# RasPi-Hi_Power.net
KiCad netlist of a schematic drawn in EAGLE
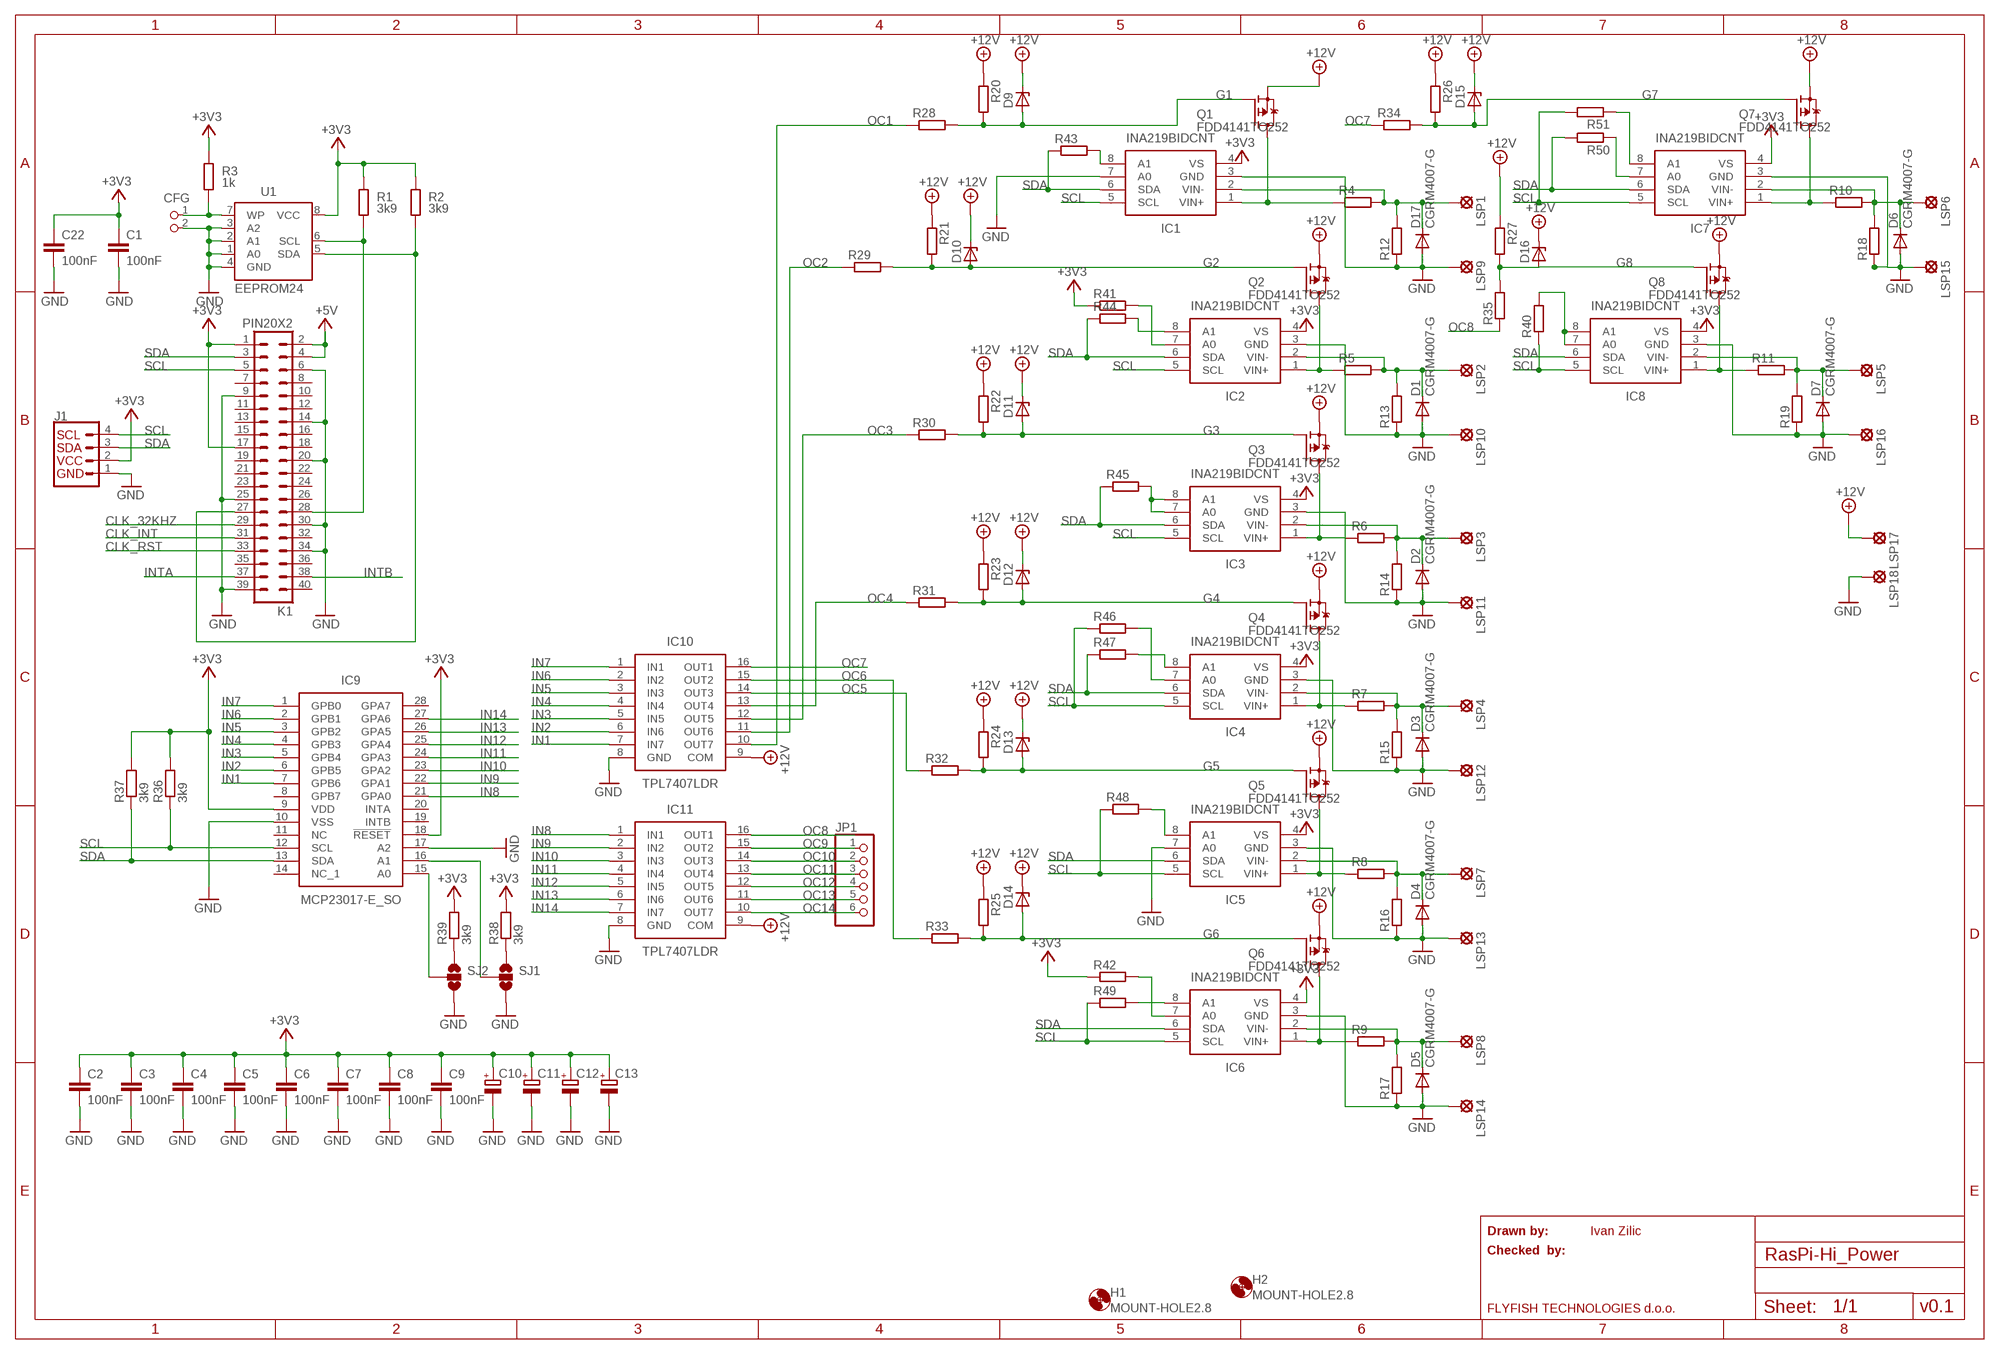
[diagram p0: schematic, sheet 1]

(export (version "E")
  (design (tool "Eeschema 10.0.6"))
  (components
    (comp (ref "C1")
      (value "100nF")
      (footprint "eagle-import:C0805K")
      (libsource (lib "eagle-import") (part "C-EUC0805K"))
    )
    (comp (ref "C2")
      (value "100nF")
      (footprint "eagle-import:C0805K")
      (libsource (lib "eagle-import") (part "C-EUC0805K"))
    )
    (comp (ref "C3")
      (value "100nF")
      (footprint "eagle-import:C0805K")
      (libsource (lib "eagle-import") (part "C-EUC0805K"))
    )
    (comp (ref "C4")
      (value "100nF")
      (footprint "eagle-import:C0805K")
      (libsource (lib "eagle-import") (part "C-EUC0805K"))
    )
    (comp (ref "C5")
      (value "100nF")
      (footprint "eagle-import:C0805K")
      (libsource (lib "eagle-import") (part "C-EUC0805K"))
    )
    (comp (ref "C6")
      (value "100nF")
      (footprint "eagle-import:C0805K")
      (libsource (lib "eagle-import") (part "C-EUC0805K"))
    )
    (comp (ref "C7")
      (value "100nF")
      (footprint "eagle-import:C0805K")
      (libsource (lib "eagle-import") (part "C-EUC0805K"))
    )
    (comp (ref "C8")
      (value "100nF")
      (footprint "eagle-import:C0805K")
      (libsource (lib "eagle-import") (part "C-EUC0805K"))
    )
    (comp (ref "C9")
      (value "100nF")
      (footprint "eagle-import:C0805K")
      (libsource (lib "eagle-import") (part "C-EUC0805K"))
    )
    (comp (ref "C10")
      (value "CPOL-EUSMCD")
      (footprint "eagle-import:SMC_D")
      (libsource (lib "eagle-import") (part "CPOL-EUSMCD"))
    )
    (comp (ref "C11")
      (value "CPOL-EUSMCD")
      (footprint "eagle-import:SMC_D")
      (libsource (lib "eagle-import") (part "CPOL-EUSMCD"))
    )
    (comp (ref "C12")
      (value "CPOL-EUSMCD")
      (footprint "eagle-import:SMC_D")
      (libsource (lib "eagle-import") (part "CPOL-EUSMCD"))
    )
    (comp (ref "C13")
      (value "CPOL-EUSMCD")
      (footprint "eagle-import:SMC_D")
      (libsource (lib "eagle-import") (part "CPOL-EUSMCD"))
    )
    (comp (ref "C22")
      (value "100nF")
      (footprint "eagle-import:C0805K")
      (libsource (lib "eagle-import") (part "C-EUC0805K"))
    )
    (comp (ref "CFG")
      (value "PIN2_100")
      (footprint "eagle-import:PIN_W_2")
      (libsource (lib "eagle-import") (part "PIN2_100"))
    )
    (comp (ref "D1")
      (value "CGRM4007-G")
      (footprint "eagle-import:SOD-123_MINI-SMA")
      (libsource (lib "eagle-import") (part "CGRM400-G7"))
    )
    (comp (ref "D2")
      (value "CGRM4007-G")
      (footprint "eagle-import:SOD-123_MINI-SMA")
      (libsource (lib "eagle-import") (part "CGRM400-G7"))
    )
    (comp (ref "D3")
      (value "CGRM4007-G")
      (footprint "eagle-import:SOD-123_MINI-SMA")
      (libsource (lib "eagle-import") (part "CGRM400-G7"))
    )
    (comp (ref "D4")
      (value "CGRM4007-G")
      (footprint "eagle-import:SOD-123_MINI-SMA")
      (libsource (lib "eagle-import") (part "CGRM400-G7"))
    )
    (comp (ref "D5")
      (value "CGRM4007-G")
      (footprint "eagle-import:SOD-123_MINI-SMA")
      (libsource (lib "eagle-import") (part "CGRM400-G7"))
    )
    (comp (ref "D6")
      (value "CGRM4007-G")
      (footprint "eagle-import:SOD-123_MINI-SMA")
      (libsource (lib "eagle-import") (part "CGRM400-G7"))
    )
    (comp (ref "D7")
      (value "CGRM4007-G")
      (footprint "eagle-import:SOD-123_MINI-SMA")
      (libsource (lib "eagle-import") (part "CGRM400-G7"))
    )
    (comp (ref "D9")
      (value "ZENER-DIODESOT23")
      (footprint "eagle-import:SOT23")
      (libsource (lib "eagle-import") (part "ZENER-DIODESOT23"))
    )
    (comp (ref "D10")
      (value "ZENER-DIODESOT23")
      (footprint "eagle-import:SOT23")
      (libsource (lib "eagle-import") (part "ZENER-DIODESOT23"))
    )
    (comp (ref "D11")
      (value "ZENER-DIODESOT23")
      (footprint "eagle-import:SOT23")
      (libsource (lib "eagle-import") (part "ZENER-DIODESOT23"))
    )
    (comp (ref "D12")
      (value "ZENER-DIODESOT23")
      (footprint "eagle-import:SOT23")
      (libsource (lib "eagle-import") (part "ZENER-DIODESOT23"))
    )
    (comp (ref "D13")
      (value "ZENER-DIODESOT23")
      (footprint "eagle-import:SOT23")
      (libsource (lib "eagle-import") (part "ZENER-DIODESOT23"))
    )
    (comp (ref "D14")
      (value "ZENER-DIODESOT23")
      (footprint "eagle-import:SOT23")
      (libsource (lib "eagle-import") (part "ZENER-DIODESOT23"))
    )
    (comp (ref "D15")
      (value "ZENER-DIODESOT23")
      (footprint "eagle-import:SOT23")
      (libsource (lib "eagle-import") (part "ZENER-DIODESOT23"))
    )
    (comp (ref "D16")
      (value "ZENER-DIODESOT23")
      (footprint "eagle-import:SOT23")
      (libsource (lib "eagle-import") (part "ZENER-DIODESOT23"))
    )
    (comp (ref "D17")
      (value "CGRM4007-G")
      (footprint "eagle-import:SOD-123_MINI-SMA")
      (libsource (lib "eagle-import") (part "CGRM400-G7"))
    )
    (comp (ref "H1")
      (value "MOUNT-HOLE2.8")
      (footprint "eagle-import:2,8")
      (libsource (lib "eagle-import") (part "MOUNT-HOLE2.8"))
    )
    (comp (ref "H2")
      (value "MOUNT-HOLE2.8")
      (footprint "eagle-import:2,8")
      (libsource (lib "eagle-import") (part "MOUNT-HOLE2.8"))
    )
    (comp (ref "IC1")
      (value "INA219BIDCNT")
      (footprint "eagle-import:SOT65P280X145-8N")
      (fields (field (name "RS_PART_NUMBER") "7300556P"))
      (libsource (lib "eagle-import") (part "INA219BIDCNT"))
    )
    (comp (ref "IC2")
      (value "INA219BIDCNT")
      (footprint "eagle-import:SOT65P280X145-8N")
      (fields (field (name "RS_PART_NUMBER") "7300556P"))
      (libsource (lib "eagle-import") (part "INA219BIDCNT"))
    )
    (comp (ref "IC3")
      (value "INA219BIDCNT")
      (footprint "eagle-import:SOT65P280X145-8N")
      (fields (field (name "RS_PART_NUMBER") "7300556P"))
      (libsource (lib "eagle-import") (part "INA219BIDCNT"))
    )
    (comp (ref "IC4")
      (value "INA219BIDCNT")
      (footprint "eagle-import:SOT65P280X145-8N")
      (fields (field (name "RS_PART_NUMBER") "7300556P"))
      (libsource (lib "eagle-import") (part "INA219BIDCNT"))
    )
    (comp (ref "IC5")
      (value "INA219BIDCNT")
      (footprint "eagle-import:SOT65P280X145-8N")
      (fields (field (name "RS_PART_NUMBER") "7300556P"))
      (libsource (lib "eagle-import") (part "INA219BIDCNT"))
    )
    (comp (ref "IC6")
      (value "INA219BIDCNT")
      (footprint "eagle-import:SOT65P280X145-8N")
      (fields (field (name "RS_PART_NUMBER") "7300556P"))
      (libsource (lib "eagle-import") (part "INA219BIDCNT"))
    )
    (comp (ref "IC7")
      (value "INA219BIDCNT")
      (footprint "eagle-import:SOT65P280X145-8N")
      (fields (field (name "RS_PART_NUMBER") "7300556P"))
      (libsource (lib "eagle-import") (part "INA219BIDCNT"))
    )
    (comp (ref "IC8")
      (value "INA219BIDCNT")
      (footprint "eagle-import:SOT65P280X145-8N")
      (fields (field (name "RS_PART_NUMBER") "7300556P"))
      (libsource (lib "eagle-import") (part "INA219BIDCNT"))
    )
    (comp (ref "IC9")
      (value "MCP23017-E_SO")
      (footprint "eagle-import:SOIC127P1030X265-28N")
      (fields
        (field (name "MANUFACTURER_PART_NUMBER") "MCP23017-E/SO")
        (field (name "RS_PART_NUMBER") "0403816P")
      )
      (libsource (lib "eagle-import") (part "MCP23017-E_SO"))
    )
    (comp (ref "IC10")
      (value "TPL7407LDR")
      (footprint "eagle-import:SOIC127P600X175-16N")
      (libsource (lib "eagle-import") (part "TPL7407LDR"))
    )
    (comp (ref "IC11")
      (value "TPL7407LDR")
      (footprint "eagle-import:SOIC127P600X175-16N")
      (libsource (lib "eagle-import") (part "TPL7407LDR"))
    )
    (comp (ref "J1")
      (value "I2C_STANDARD")
      (footprint "eagle-import:1X04")
      (libsource (lib "eagle-import") (part "I2C_STANDARD"))
    )
    (comp (ref "JP1")
      (value "PINHD-1X6")
      (footprint "eagle-import:1X06")
      (libsource (lib "eagle-import") (part "PINHD-1X6"))
    )
    (comp (ref "K1")
      (value "PIN20X2")
      (footprint "eagle-import:PIN_20X2")
      (libsource (lib "eagle-import") (part "PIN20X2"))
    )
    (comp (ref "LSP1")
      (value "SE13")
      (footprint "eagle-import:SE13")
      (libsource (lib "eagle-import") (part "SE13"))
    )
    (comp (ref "LSP2")
      (value "SE13")
      (footprint "eagle-import:SE13")
      (libsource (lib "eagle-import") (part "SE13"))
    )
    (comp (ref "LSP3")
      (value "SE13")
      (footprint "eagle-import:SE13")
      (libsource (lib "eagle-import") (part "SE13"))
    )
    (comp (ref "LSP4")
      (value "SE13")
      (footprint "eagle-import:SE13")
      (libsource (lib "eagle-import") (part "SE13"))
    )
    (comp (ref "LSP5")
      (value "SE13")
      (footprint "eagle-import:SE13")
      (libsource (lib "eagle-import") (part "SE13"))
    )
    (comp (ref "LSP6")
      (value "SE13")
      (footprint "eagle-import:SE13")
      (libsource (lib "eagle-import") (part "SE13"))
    )
    (comp (ref "LSP7")
      (value "SE13")
      (footprint "eagle-import:SE13")
      (libsource (lib "eagle-import") (part "SE13"))
    )
    (comp (ref "LSP8")
      (value "SE13")
      (footprint "eagle-import:SE13")
      (libsource (lib "eagle-import") (part "SE13"))
    )
    (comp (ref "LSP9")
      (value "SE13")
      (footprint "eagle-import:SE13")
      (libsource (lib "eagle-import") (part "SE13"))
    )
    (comp (ref "LSP10")
      (value "SE13")
      (footprint "eagle-import:SE13")
      (libsource (lib "eagle-import") (part "SE13"))
    )
    (comp (ref "LSP11")
      (value "SE13")
      (footprint "eagle-import:SE13")
      (libsource (lib "eagle-import") (part "SE13"))
    )
    (comp (ref "LSP12")
      (value "SE13")
      (footprint "eagle-import:SE13")
      (libsource (lib "eagle-import") (part "SE13"))
    )
    (comp (ref "LSP13")
      (value "SE13")
      (footprint "eagle-import:SE13")
      (libsource (lib "eagle-import") (part "SE13"))
    )
    (comp (ref "LSP14")
      (value "SE13")
      (footprint "eagle-import:SE13")
      (libsource (lib "eagle-import") (part "SE13"))
    )
    (comp (ref "LSP15")
      (value "SE13")
      (footprint "eagle-import:SE13")
      (libsource (lib "eagle-import") (part "SE13"))
    )
    (comp (ref "LSP16")
      (value "SE13")
      (footprint "eagle-import:SE13")
      (libsource (lib "eagle-import") (part "SE13"))
    )
    (comp (ref "LSP17")
      (value "SE13")
      (footprint "eagle-import:SE13")
      (libsource (lib "eagle-import") (part "SE13"))
    )
    (comp (ref "LSP18")
      (value "SE13")
      (footprint "eagle-import:SE13")
      (libsource (lib "eagle-import") (part "SE13"))
    )
    (comp (ref "Q1")
      (value "FDD4141TO252")
      (footprint "eagle-import:TO252")
      (libsource (lib "eagle-import") (part "FDD4141TO252"))
    )
    (comp (ref "Q2")
      (value "FDD4141TO252")
      (footprint "eagle-import:TO252")
      (libsource (lib "eagle-import") (part "FDD4141TO252"))
    )
    (comp (ref "Q3")
      (value "FDD4141TO252")
      (footprint "eagle-import:TO252")
      (libsource (lib "eagle-import") (part "FDD4141TO252"))
    )
    (comp (ref "Q4")
      (value "FDD4141TO252")
      (footprint "eagle-import:TO252")
      (libsource (lib "eagle-import") (part "FDD4141TO252"))
    )
    (comp (ref "Q5")
      (value "FDD4141TO252")
      (footprint "eagle-import:TO252")
      (libsource (lib "eagle-import") (part "FDD4141TO252"))
    )
    (comp (ref "Q6")
      (value "FDD4141TO252")
      (footprint "eagle-import:TO252")
      (libsource (lib "eagle-import") (part "FDD4141TO252"))
    )
    (comp (ref "Q7")
      (value "FDD4141TO252")
      (footprint "eagle-import:TO252")
      (libsource (lib "eagle-import") (part "FDD4141TO252"))
    )
    (comp (ref "Q8")
      (value "FDD4141TO252")
      (footprint "eagle-import:TO252")
      (libsource (lib "eagle-import") (part "FDD4141TO252"))
    )
    (comp (ref "R1")
      (value "3k9")
      (footprint "eagle-import:M0805")
      (fields (field (name "TOLERANCE") "5%"))
      (libsource (lib "eagle-import") (part "resistor_348_R-EU_M0805"))
    )
    (comp (ref "R2")
      (value "3k9")
      (footprint "eagle-import:M0805")
      (fields (field (name "TOLERANCE") "5%"))
      (libsource (lib "eagle-import") (part "resistor_348_R-EU_M0805"))
    )
    (comp (ref "R3")
      (value "1k")
      (footprint "eagle-import:M0805")
      (fields (field (name "TOLERANCE") "5%"))
      (libsource (lib "eagle-import") (part "resistor_348_R-EU_M0805"))
    )
    (comp (ref "R4")
      (value "R-EU_R1210")
      (footprint "eagle-import:R1210")
      (libsource (lib "eagle-import") (part "R-EU_R1210"))
    )
    (comp (ref "R5")
      (value "R-EU_R1210")
      (footprint "eagle-import:R1210")
      (libsource (lib "eagle-import") (part "R-EU_R1210"))
    )
    (comp (ref "R6")
      (value "R-EU_R1210")
      (footprint "eagle-import:R1210")
      (libsource (lib "eagle-import") (part "R-EU_R1210"))
    )
    (comp (ref "R7")
      (value "R-EU_R1210")
      (footprint "eagle-import:R1210")
      (libsource (lib "eagle-import") (part "R-EU_R1210"))
    )
    (comp (ref "R8")
      (value "R-EU_R1210")
      (footprint "eagle-import:R1210")
      (libsource (lib "eagle-import") (part "R-EU_R1210"))
    )
    (comp (ref "R9")
      (value "R-EU_R1210")
      (footprint "eagle-import:R1210")
      (libsource (lib "eagle-import") (part "R-EU_R1210"))
    )
    (comp (ref "R10")
      (value "R-EU_R1210")
      (footprint "eagle-import:R1210")
      (libsource (lib "eagle-import") (part "R-EU_R1210"))
    )
    (comp (ref "R11")
      (value "R-EU_R1210")
      (footprint "eagle-import:R1210")
      (libsource (lib "eagle-import") (part "R-EU_R1210"))
    )
    (comp (ref "R12")
      (value "R-EU_R0805")
      (footprint "eagle-import:R0805")
      (libsource (lib "eagle-import") (part "R-EU_R0805"))
    )
    (comp (ref "R13")
      (value "R-EU_R0805")
      (footprint "eagle-import:R0805")
      (libsource (lib "eagle-import") (part "R-EU_R0805"))
    )
    (comp (ref "R14")
      (value "R-EU_R0805")
      (footprint "eagle-import:R0805")
      (libsource (lib "eagle-import") (part "R-EU_R0805"))
    )
    (comp (ref "R15")
      (value "R-EU_R0805")
      (footprint "eagle-import:R0805")
      (libsource (lib "eagle-import") (part "R-EU_R0805"))
    )
    (comp (ref "R16")
      (value "R-EU_R0805")
      (footprint "eagle-import:R0805")
      (libsource (lib "eagle-import") (part "R-EU_R0805"))
    )
    (comp (ref "R17")
      (value "R-EU_R0805")
      (footprint "eagle-import:R0805")
      (libsource (lib "eagle-import") (part "R-EU_R0805"))
    )
    (comp (ref "R18")
      (value "R-EU_R0805")
      (footprint "eagle-import:R0805")
      (libsource (lib "eagle-import") (part "R-EU_R0805"))
    )
    (comp (ref "R19")
      (value "R-EU_R0805")
      (footprint "eagle-import:R0805")
      (libsource (lib "eagle-import") (part "R-EU_R0805"))
    )
    (comp (ref "R20")
      (value "R-EU_R0805")
      (footprint "eagle-import:R0805")
      (libsource (lib "eagle-import") (part "R-EU_R0805"))
    )
    (comp (ref "R21")
      (value "R-EU_R0805")
      (footprint "eagle-import:R0805")
      (libsource (lib "eagle-import") (part "R-EU_R0805"))
    )
    (comp (ref "R22")
      (value "R-EU_R0805")
      (footprint "eagle-import:R0805")
      (libsource (lib "eagle-import") (part "R-EU_R0805"))
    )
    (comp (ref "R23")
      (value "R-EU_R0805")
      (footprint "eagle-import:R0805")
      (libsource (lib "eagle-import") (part "R-EU_R0805"))
    )
    (comp (ref "R24")
      (value "R-EU_R0805")
      (footprint "eagle-import:R0805")
      (libsource (lib "eagle-import") (part "R-EU_R0805"))
    )
    (comp (ref "R25")
      (value "R-EU_R0805")
      (footprint "eagle-import:R0805")
      (libsource (lib "eagle-import") (part "R-EU_R0805"))
    )
    (comp (ref "R26")
      (value "R-EU_R0805")
      (footprint "eagle-import:R0805")
      (libsource (lib "eagle-import") (part "R-EU_R0805"))
    )
    (comp (ref "R27")
      (value "R-EU_R0805")
      (footprint "eagle-import:R0805")
      (libsource (lib "eagle-import") (part "R-EU_R0805"))
    )
    (comp (ref "R28")
      (value "R-EU_R0805")
      (footprint "eagle-import:R0805")
      (libsource (lib "eagle-import") (part "R-EU_R0805"))
    )
    (comp (ref "R29")
      (value "R-EU_R0805")
      (footprint "eagle-import:R0805")
      (libsource (lib "eagle-import") (part "R-EU_R0805"))
    )
    (comp (ref "R30")
      (value "R-EU_R0805")
      (footprint "eagle-import:R0805")
      (libsource (lib "eagle-import") (part "R-EU_R0805"))
    )
    (comp (ref "R31")
      (value "R-EU_R0805")
      (footprint "eagle-import:R0805")
      (libsource (lib "eagle-import") (part "R-EU_R0805"))
    )
    (comp (ref "R32")
      (value "R-EU_R0805")
      (footprint "eagle-import:R0805")
      (libsource (lib "eagle-import") (part "R-EU_R0805"))
    )
    (comp (ref "R33")
      (value "R-EU_R0805")
      (footprint "eagle-import:R0805")
      (libsource (lib "eagle-import") (part "R-EU_R0805"))
    )
    (comp (ref "R34")
      (value "R-EU_R0805")
      (footprint "eagle-import:R0805")
      (libsource (lib "eagle-import") (part "R-EU_R0805"))
    )
    (comp (ref "R35")
      (value "R-EU_R0805")
      (footprint "eagle-import:R0805")
      (libsource (lib "eagle-import") (part "R-EU_R0805"))
    )
    (comp (ref "R36")
      (value "3k9")
      (footprint "eagle-import:M0805")
      (fields (field (name "TOLERANCE") "5%"))
      (libsource (lib "eagle-import") (part "resistor_348_R-EU_M0805"))
    )
    (comp (ref "R37")
      (value "3k9")
      (footprint "eagle-import:M0805")
      (fields (field (name "TOLERANCE") "5%"))
      (libsource (lib "eagle-import") (part "resistor_348_R-EU_M0805"))
    )
    (comp (ref "R38")
      (value "3k9")
      (footprint "eagle-import:R0603")
      (fields (field (name "TOLERANCE") "5%"))
      (libsource (lib "eagle-import") (part "resistor_348_R-EU_R0603"))
    )
    (comp (ref "R39")
      (value "3k9")
      (footprint "eagle-import:R0603")
      (fields (field (name "TOLERANCE") "5%"))
      (libsource (lib "eagle-import") (part "resistor_348_R-EU_R0603"))
    )
    (comp (ref "R40")
      (value "R-EU_R0603")
      (footprint "eagle-import:R0603")
      (libsource (lib "eagle-import") (part "R-EU_R0603"))
    )
    (comp (ref "R41")
      (value "R-EU_R0805")
      (footprint "eagle-import:R0805")
      (libsource (lib "eagle-import") (part "R-EU_R0805"))
    )
    (comp (ref "R42")
      (value "R-EU_R0805")
      (footprint "eagle-import:R0805")
      (libsource (lib "eagle-import") (part "R-EU_R0805"))
    )
    (comp (ref "R43")
      (value "R-EU_R0805")
      (footprint "eagle-import:R0805")
      (libsource (lib "eagle-import") (part "R-EU_R0805"))
    )
    (comp (ref "R44")
      (value "R-EU_R0805")
      (footprint "eagle-import:R0805")
      (libsource (lib "eagle-import") (part "R-EU_R0805"))
    )
    (comp (ref "R45")
      (value "R-EU_R0805")
      (footprint "eagle-import:R0805")
      (libsource (lib "eagle-import") (part "R-EU_R0805"))
    )
    (comp (ref "R46")
      (value "R-EU_R0805")
      (footprint "eagle-import:R0805")
      (libsource (lib "eagle-import") (part "R-EU_R0805"))
    )
    (comp (ref "R47")
      (value "R-EU_R0805")
      (footprint "eagle-import:R0805")
      (libsource (lib "eagle-import") (part "R-EU_R0805"))
    )
    (comp (ref "R48")
      (value "R-EU_R0805")
      (footprint "eagle-import:R0805")
      (libsource (lib "eagle-import") (part "R-EU_R0805"))
    )
    (comp (ref "R49")
      (value "R-EU_R0805")
      (footprint "eagle-import:R0805")
      (libsource (lib "eagle-import") (part "R-EU_R0805"))
    )
    (comp (ref "R50")
      (value "R-EU_R0805")
      (footprint "eagle-import:R0805")
      (libsource (lib "eagle-import") (part "R-EU_R0805"))
    )
    (comp (ref "R51")
      (value "R-EU_R0805")
      (footprint "eagle-import:R0805")
      (libsource (lib "eagle-import") (part "R-EU_R0805"))
    )
    (comp (ref "SJ1")
      (value "SOLDERJUMPER_2WAYT")
      (footprint "eagle-import:SJ_2")
      (libsource (lib "eagle-import") (part "SOLDERJUMPER_2WAYT"))
    )
    (comp (ref "SJ2")
      (value "SOLDERJUMPER_2WAYT")
      (footprint "eagle-import:SJ_2")
      (libsource (lib "eagle-import") (part "SOLDERJUMPER_2WAYT"))
    )
    (comp (ref "U1")
      (value "EEPROM24")
      (footprint "eagle-import:SOIC8")
      (libsource (lib "eagle-import") (part "EEPROM24"))
    )
  )
  (nets
    (net (code "1") (name "+3V3") (class "Default")
      (node (ref "C1") (pin "1") (pinfunction "1_1") (pintype "passive"))
      (node (ref "C10") (pin "+") (pinfunction "+_+") (pintype "passive"))
      (node (ref "C11") (pin "+") (pinfunction "+_+") (pintype "passive"))
      (node (ref "C12") (pin "+") (pinfunction "+_+") (pintype "passive"))
      (node (ref "C13") (pin "+") (pinfunction "+_+") (pintype "passive"))
      (node (ref "C2") (pin "1") (pinfunction "1_1") (pintype "passive"))
      (node (ref "C22") (pin "1") (pinfunction "1_1") (pintype "passive"))
      (node (ref "C3") (pin "1") (pinfunction "1_1") (pintype "passive"))
      (node (ref "C4") (pin "1") (pinfunction "1_1") (pintype "passive"))
      (node (ref "C5") (pin "1") (pinfunction "1_1") (pintype "passive"))
      (node (ref "C6") (pin "1") (pinfunction "1_1") (pintype "passive"))
      (node (ref "C7") (pin "1") (pinfunction "1_1") (pintype "passive"))
      (node (ref "C8") (pin "1") (pinfunction "1_1") (pintype "passive"))
      (node (ref "C9") (pin "1") (pinfunction "1_1") (pintype "passive"))
      (node (ref "IC1") (pin "4") (pinfunction "VS_4") (pintype "passive"))
      (node (ref "IC2") (pin "4") (pinfunction "VS_4") (pintype "passive"))
      (node (ref "IC3") (pin "4") (pinfunction "VS_4") (pintype "passive"))
      (node (ref "IC4") (pin "4") (pinfunction "VS_4") (pintype "passive"))
      (node (ref "IC5") (pin "4") (pinfunction "VS_4") (pintype "passive"))
      (node (ref "IC6") (pin "4") (pinfunction "VS_4") (pintype "passive"))
      (node (ref "IC7") (pin "4") (pinfunction "VS_4") (pintype "passive"))
      (node (ref "IC8") (pin "4") (pinfunction "VS_4") (pintype "passive"))
      (node (ref "IC9") (pin "18") (pinfunction "~{RESET}_18") (pintype "passive"))
      (node (ref "IC9") (pin "9") (pinfunction "VDD_9") (pintype "power_in"))
      (node (ref "J1") (pin "2") (pinfunction "2_2") (pintype "power_in"))
      (node (ref "K1") (pin "1") (pinfunction "1_1") (pintype "passive"))
      (node (ref "K1") (pin "17") (pinfunction "17_17") (pintype "passive"))
      (node (ref "R1") (pin "2") (pinfunction "2_2") (pintype "passive"))
      (node (ref "R2") (pin "2") (pinfunction "2_2") (pintype "passive"))
      (node (ref "R3") (pin "2") (pinfunction "2_2") (pintype "passive"))
      (node (ref "R36") (pin "2") (pinfunction "2_2") (pintype "passive"))
      (node (ref "R37") (pin "2") (pinfunction "2_2") (pintype "passive"))
      (node (ref "R38") (pin "2") (pinfunction "2_2") (pintype "passive"))
      (node (ref "R39") (pin "2") (pinfunction "2_2") (pintype "passive"))
      (node (ref "R41") (pin "1") (pinfunction "1_1") (pintype "passive"))
      (node (ref "R42") (pin "1") (pinfunction "1_1") (pintype "passive"))
      (node (ref "U1") (pin "8") (pinfunction "VCC_8") (pintype "power_in"))
    )
    (net (code "2") (name "+5V") (class "Default")
      (node (ref "K1") (pin "2") (pinfunction "2_2") (pintype "passive"))
      (node (ref "K1") (pin "4") (pinfunction "4_4") (pintype "passive"))
    )
    (net (code "3") (name "+12V") (class "Default")
      (node (ref "D10") (pin "3") (pinfunction "C_3") (pintype "passive"))
      (node (ref "D11") (pin "3") (pinfunction "C_3") (pintype "passive"))
      (node (ref "D12") (pin "3") (pinfunction "C_3") (pintype "passive"))
      (node (ref "D13") (pin "3") (pinfunction "C_3") (pintype "passive"))
      (node (ref "D14") (pin "3") (pinfunction "C_3") (pintype "passive"))
      (node (ref "D15") (pin "3") (pinfunction "C_3") (pintype "passive"))
      (node (ref "D16") (pin "3") (pinfunction "C_3") (pintype "passive"))
      (node (ref "D9") (pin "3") (pinfunction "C_3") (pintype "passive"))
      (node (ref "IC10") (pin "9") (pinfunction "COM_9") (pintype "power_in"))
      (node (ref "IC11") (pin "9") (pinfunction "COM_9") (pintype "power_in"))
      (node (ref "LSP17") (pin "MP") (pinfunction "MP_MP") (pintype "passive"))
      (node (ref "Q1") (pin "2") (pinfunction "S_2") (pintype "passive"))
      (node (ref "Q2") (pin "2") (pinfunction "S_2") (pintype "passive"))
      (node (ref "Q3") (pin "2") (pinfunction "S_2") (pintype "passive"))
      (node (ref "Q4") (pin "2") (pinfunction "S_2") (pintype "passive"))
      (node (ref "Q5") (pin "2") (pinfunction "S_2") (pintype "passive"))
      (node (ref "Q6") (pin "2") (pinfunction "S_2") (pintype "passive"))
      (node (ref "Q7") (pin "2") (pinfunction "S_2") (pintype "passive"))
      (node (ref "Q8") (pin "2") (pinfunction "S_2") (pintype "passive"))
      (node (ref "R20") (pin "1") (pinfunction "1_1") (pintype "passive"))
      (node (ref "R21") (pin "1") (pinfunction "1_1") (pintype "passive"))
      (node (ref "R22") (pin "1") (pinfunction "1_1") (pintype "passive"))
      (node (ref "R23") (pin "1") (pinfunction "1_1") (pintype "passive"))
      (node (ref "R24") (pin "1") (pinfunction "1_1") (pintype "passive"))
      (node (ref "R25") (pin "1") (pinfunction "1_1") (pintype "passive"))
      (node (ref "R26") (pin "1") (pinfunction "1_1") (pintype "passive"))
      (node (ref "R27") (pin "1") (pinfunction "1_1") (pintype "passive"))
    )
    (net (code "4") (name "/CLK_32KHZ") (class "Default")
      (node (ref "K1") (pin "29") (pinfunction "29_29") (pintype "passive"))
    )
    (net (code "5") (name "/CLK_INT") (class "Default")
      (node (ref "K1") (pin "31") (pinfunction "31_31") (pintype "passive"))
    )
    (net (code "6") (name "/CLK_RST") (class "Default")
      (node (ref "K1") (pin "33") (pinfunction "33_33") (pintype "passive"))
    )
    (net (code "7") (name "/G1") (class "Default")
      (node (ref "D9") (pin "1") (pinfunction "A_1") (pintype "passive"))
      (node (ref "Q1") (pin "1") (pinfunction "G_1") (pintype "passive"))
      (node (ref "R20") (pin "2") (pinfunction "2_2") (pintype "passive"))
      (node (ref "R28") (pin "2") (pinfunction "2_2") (pintype "passive"))
    )
    (net (code "8") (name "/G2") (class "Default")
      (node (ref "D10") (pin "1") (pinfunction "A_1") (pintype "passive"))
      (node (ref "Q2") (pin "1") (pinfunction "G_1") (pintype "passive"))
      (node (ref "R21") (pin "2") (pinfunction "2_2") (pintype "passive"))
      (node (ref "R29") (pin "2") (pinfunction "2_2") (pintype "passive"))
    )
    (net (code "9") (name "/G3") (class "Default")
      (node (ref "D11") (pin "1") (pinfunction "A_1") (pintype "passive"))
      (node (ref "Q3") (pin "1") (pinfunction "G_1") (pintype "passive"))
      (node (ref "R22") (pin "2") (pinfunction "2_2") (pintype "passive"))
      (node (ref "R30") (pin "2") (pinfunction "2_2") (pintype "passive"))
    )
    (net (code "10") (name "/G4") (class "Default")
      (node (ref "D12") (pin "1") (pinfunction "A_1") (pintype "passive"))
      (node (ref "Q4") (pin "1") (pinfunction "G_1") (pintype "passive"))
      (node (ref "R23") (pin "2") (pinfunction "2_2") (pintype "passive"))
      (node (ref "R31") (pin "2") (pinfunction "2_2") (pintype "passive"))
    )
    (net (code "11") (name "/G5") (class "Default")
      (node (ref "D13") (pin "1") (pinfunction "A_1") (pintype "passive"))
      (node (ref "Q5") (pin "1") (pinfunction "G_1") (pintype "passive"))
      (node (ref "R24") (pin "2") (pinfunction "2_2") (pintype "passive"))
      (node (ref "R32") (pin "2") (pinfunction "2_2") (pintype "passive"))
    )
    (net (code "12") (name "/G6") (class "Default")
      (node (ref "D14") (pin "1") (pinfunction "A_1") (pintype "passive"))
      (node (ref "Q6") (pin "1") (pinfunction "G_1") (pintype "passive"))
      (node (ref "R25") (pin "2") (pinfunction "2_2") (pintype "passive"))
      (node (ref "R33") (pin "2") (pinfunction "2_2") (pintype "passive"))
    )
    (net (code "13") (name "/G7") (class "Default")
      (node (ref "D15") (pin "1") (pinfunction "A_1") (pintype "passive"))
      (node (ref "Q7") (pin "1") (pinfunction "G_1") (pintype "passive"))
      (node (ref "R26") (pin "2") (pinfunction "2_2") (pintype "passive"))
      (node (ref "R34") (pin "2") (pinfunction "2_2") (pintype "passive"))
    )
    (net (code "14") (name "/G8") (class "Default")
      (node (ref "D16") (pin "1") (pinfunction "A_1") (pintype "passive"))
      (node (ref "Q8") (pin "1") (pinfunction "G_1") (pintype "passive"))
      (node (ref "R27") (pin "2") (pinfunction "2_2") (pintype "passive"))
      (node (ref "R35") (pin "2") (pinfunction "2_2") (pintype "passive"))
    )
    (net (code "15") (name "/IN1") (class "Default")
      (node (ref "IC10") (pin "7") (pinfunction "IN7_7") (pintype "input"))
      (node (ref "IC9") (pin "7") (pinfunction "GPB6_7") (pintype "passive"))
    )
    (net (code "16") (name "/IN2") (class "Default")
      (node (ref "IC10") (pin "6") (pinfunction "IN6_6") (pintype "input"))
      (node (ref "IC9") (pin "6") (pinfunction "GPB5_6") (pintype "passive"))
    )
    (net (code "17") (name "/IN3") (class "Default")
      (node (ref "IC10") (pin "5") (pinfunction "IN5_5") (pintype "input"))
      (node (ref "IC9") (pin "5") (pinfunction "GPB4_5") (pintype "passive"))
    )
    (net (code "18") (name "/IN4") (class "Default")
      (node (ref "IC10") (pin "4") (pinfunction "IN4_4") (pintype "input"))
      (node (ref "IC9") (pin "4") (pinfunction "GPB3_4") (pintype "passive"))
    )
    (net (code "19") (name "/IN5") (class "Default")
      (node (ref "IC10") (pin "3") (pinfunction "IN3_3") (pintype "input"))
      (node (ref "IC9") (pin "3") (pinfunction "GPB2_3") (pintype "passive"))
    )
    (net (code "20") (name "/IN6") (class "Default")
      (node (ref "IC10") (pin "2") (pinfunction "IN2_2") (pintype "input"))
      (node (ref "IC9") (pin "2") (pinfunction "GPB1_2") (pintype "passive"))
    )
    (net (code "21") (name "/IN7") (class "Default")
      (node (ref "IC10") (pin "1") (pinfunction "IN1_1") (pintype "input"))
      (node (ref "IC9") (pin "1") (pinfunction "GPB0_1") (pintype "passive"))
    )
    (net (code "22") (name "/IN8") (class "Default")
      (node (ref "IC11") (pin "1") (pinfunction "IN1_1") (pintype "input"))
      (node (ref "IC9") (pin "21") (pinfunction "GPA0_21") (pintype "passive"))
    )
    (net (code "23") (name "/IN9") (class "Default")
      (node (ref "IC11") (pin "2") (pinfunction "IN2_2") (pintype "input"))
      (node (ref "IC9") (pin "22") (pinfunction "GPA1_22") (pintype "passive"))
    )
    (net (code "24") (name "/IN10") (class "Default")
      (node (ref "IC11") (pin "3") (pinfunction "IN3_3") (pintype "input"))
      (node (ref "IC9") (pin "23") (pinfunction "GPA2_23") (pintype "passive"))
    )
    (net (code "25") (name "/IN11") (class "Default")
      (node (ref "IC11") (pin "4") (pinfunction "IN4_4") (pintype "input"))
      (node (ref "IC9") (pin "24") (pinfunction "GPA3_24") (pintype "passive"))
    )
    (net (code "26") (name "/IN12") (class "Default")
      (node (ref "IC11") (pin "5") (pinfunction "IN5_5") (pintype "input"))
      (node (ref "IC9") (pin "25") (pinfunction "GPA4_25") (pintype "passive"))
    )
    (net (code "27") (name "/IN13") (class "Default")
      (node (ref "IC11") (pin "6") (pinfunction "IN6_6") (pintype "input"))
      (node (ref "IC9") (pin "26") (pinfunction "GPA5_26") (pintype "passive"))
    )
    (net (code "28") (name "/IN14") (class "Default")
      (node (ref "IC11") (pin "7") (pinfunction "IN7_7") (pintype "input"))
      (node (ref "IC9") (pin "27") (pinfunction "GPA6_27") (pintype "passive"))
    )
    (net (code "29") (name "/INTA") (class "Default")
      (node (ref "K1") (pin "37") (pinfunction "37_37") (pintype "passive"))
    )
    (net (code "30") (name "/INTB") (class "Default")
      (node (ref "K1") (pin "38") (pinfunction "38_38") (pintype "passive"))
    )
    (net (code "31") (name "/OC1") (class "Default")
      (node (ref "IC10") (pin "10") (pinfunction "OUT7_10") (pintype "passive"))
      (node (ref "R28") (pin "1") (pinfunction "1_1") (pintype "passive"))
    )
    (net (code "32") (name "/OC2") (class "Default")
      (node (ref "IC10") (pin "11") (pinfunction "OUT6_11") (pintype "passive"))
      (node (ref "R29") (pin "1") (pinfunction "1_1") (pintype "passive"))
    )
    (net (code "33") (name "/OC3") (class "Default")
      (node (ref "IC10") (pin "12") (pinfunction "OUT5_12") (pintype "passive"))
      (node (ref "R30") (pin "1") (pinfunction "1_1") (pintype "passive"))
    )
    (net (code "34") (name "/OC4") (class "Default")
      (node (ref "IC10") (pin "13") (pinfunction "OUT4_13") (pintype "passive"))
      (node (ref "R31") (pin "1") (pinfunction "1_1") (pintype "passive"))
    )
    (net (code "35") (name "/OC5") (class "Default")
      (node (ref "IC10") (pin "14") (pinfunction "OUT3_14") (pintype "passive"))
      (node (ref "R32") (pin "1") (pinfunction "1_1") (pintype "passive"))
    )
    (net (code "36") (name "/OC6") (class "Default")
      (node (ref "IC10") (pin "15") (pinfunction "OUT2_15") (pintype "passive"))
      (node (ref "R33") (pin "1") (pinfunction "1_1") (pintype "passive"))
    )
    (net (code "37") (name "/OC7") (class "Default")
      (node (ref "IC10") (pin "16") (pinfunction "OUT1_16") (pintype "passive"))
      (node (ref "R34") (pin "1") (pinfunction "1_1") (pintype "passive"))
    )
    (net (code "38") (name "/OC8") (class "Default")
      (node (ref "IC11") (pin "16") (pinfunction "OUT1_16") (pintype "passive"))
      (node (ref "R35") (pin "1") (pinfunction "1_1") (pintype "passive"))
    )
    (net (code "39") (name "/OC9") (class "Default")
      (node (ref "IC11") (pin "15") (pinfunction "OUT2_15") (pintype "passive"))
      (node (ref "JP1") (pin "1") (pinfunction "1_1") (pintype "passive"))
    )
    (net (code "40") (name "/OC10") (class "Default")
      (node (ref "IC11") (pin "14") (pinfunction "OUT3_14") (pintype "passive"))
      (node (ref "JP1") (pin "2") (pinfunction "2_2") (pintype "passive"))
    )
    (net (code "41") (name "/OC11") (class "Default")
      (node (ref "IC11") (pin "13") (pinfunction "OUT4_13") (pintype "passive"))
      (node (ref "JP1") (pin "3") (pinfunction "3_3") (pintype "passive"))
    )
    (net (code "42") (name "/OC12") (class "Default")
      (node (ref "IC11") (pin "12") (pinfunction "OUT5_12") (pintype "passive"))
      (node (ref "JP1") (pin "4") (pinfunction "4_4") (pintype "passive"))
    )
    (net (code "43") (name "/OC13") (class "Default")
      (node (ref "IC11") (pin "11") (pinfunction "OUT6_11") (pintype "passive"))
      (node (ref "JP1") (pin "5") (pinfunction "5_5") (pintype "passive"))
    )
    (net (code "44") (name "/OC14") (class "Default")
      (node (ref "IC11") (pin "10") (pinfunction "OUT7_10") (pintype "passive"))
      (node (ref "JP1") (pin "6") (pinfunction "6_6") (pintype "passive"))
    )
    (net (code "45") (name "/SCL") (class "Default")
      (node (ref "IC1") (pin "5") (pinfunction "SCL_5") (pintype "passive"))
      (node (ref "IC2") (pin "5") (pinfunction "SCL_5") (pintype "passive"))
      (node (ref "IC3") (pin "5") (pinfunction "SCL_5") (pintype "passive"))
      (node (ref "IC4") (pin "5") (pinfunction "SCL_5") (pintype "passive"))
      (node (ref "IC5") (pin "5") (pinfunction "SCL_5") (pintype "passive"))
      (node (ref "IC6") (pin "5") (pinfunction "SCL_5") (pintype "passive"))
      (node (ref "IC7") (pin "5") (pinfunction "SCL_5") (pintype "passive"))
      (node (ref "IC8") (pin "5") (pinfunction "SCL_5") (pintype "passive"))
      (node (ref "IC9") (pin "12") (pinfunction "SCL_12") (pintype "passive"))
      (node (ref "J1") (pin "4") (pinfunction "4_4") (pintype "passive"))
      (node (ref "K1") (pin "5") (pinfunction "5_5") (pintype "passive"))
      (node (ref "R36") (pin "1") (pinfunction "1_1") (pintype "passive"))
      (node (ref "R40") (pin "1") (pinfunction "1_1") (pintype "passive"))
      (node (ref "R46") (pin "1") (pinfunction "1_1") (pintype "passive"))
      (node (ref "R48") (pin "1") (pinfunction "1_1") (pintype "passive"))
      (node (ref "R49") (pin "1") (pinfunction "1_1") (pintype "passive"))
      (node (ref "R51") (pin "2") (pinfunction "2_2") (pintype "passive"))
    )
    (net (code "46") (name "/SDA") (class "Default")
      (node (ref "IC1") (pin "6") (pinfunction "SDA_6") (pintype "passive"))
      (node (ref "IC2") (pin "6") (pinfunction "SDA_6") (pintype "passive"))
      (node (ref "IC3") (pin "6") (pinfunction "SDA_6") (pintype "passive"))
      (node (ref "IC4") (pin "6") (pinfunction "SDA_6") (pintype "passive"))
      (node (ref "IC5") (pin "6") (pinfunction "SDA_6") (pintype "passive"))
      (node (ref "IC6") (pin "6") (pinfunction "SDA_6") (pintype "passive"))
      (node (ref "IC7") (pin "6") (pinfunction "SDA_6") (pintype "passive"))
      (node (ref "IC8") (pin "6") (pinfunction "SDA_6") (pintype "passive"))
      (node (ref "IC9") (pin "13") (pinfunction "SDA_13") (pintype "passive"))
      (node (ref "J1") (pin "3") (pinfunction "3_3") (pintype "passive"))
      (node (ref "K1") (pin "3") (pinfunction "3_3") (pintype "passive"))
      (node (ref "R37") (pin "1") (pinfunction "1_1") (pintype "passive"))
      (node (ref "R43") (pin "1") (pinfunction "1_1") (pintype "passive"))
      (node (ref "R44") (pin "1") (pinfunction "1_1") (pintype "passive"))
      (node (ref "R45") (pin "1") (pinfunction "1_1") (pintype "passive"))
      (node (ref "R47") (pin "1") (pinfunction "1_1") (pintype "passive"))
      (node (ref "R50") (pin "2") (pinfunction "2_2") (pintype "passive"))
    )
    (net (code "47") (name "GND") (class "Default")
      (node (ref "C1") (pin "2") (pinfunction "2_2") (pintype "passive"))
      (node (ref "C10") (pin "-") (pinfunction "-_-") (pintype "passive"))
      (node (ref "C11") (pin "-") (pinfunction "-_-") (pintype "passive"))
      (node (ref "C12") (pin "-") (pinfunction "-_-") (pintype "passive"))
      (node (ref "C13") (pin "-") (pinfunction "-_-") (pintype "passive"))
      (node (ref "C2") (pin "2") (pinfunction "2_2") (pintype "passive"))
      (node (ref "C22") (pin "2") (pinfunction "2_2") (pintype "passive"))
      (node (ref "C3") (pin "2") (pinfunction "2_2") (pintype "passive"))
      (node (ref "C4") (pin "2") (pinfunction "2_2") (pintype "passive"))
      (node (ref "C5") (pin "2") (pinfunction "2_2") (pintype "passive"))
      (node (ref "C6") (pin "2") (pinfunction "2_2") (pintype "passive"))
      (node (ref "C7") (pin "2") (pinfunction "2_2") (pintype "passive"))
      (node (ref "C8") (pin "2") (pinfunction "2_2") (pintype "passive"))
      (node (ref "C9") (pin "2") (pinfunction "2_2") (pintype "passive"))
      (node (ref "CFG") (pin "2") (pinfunction "2_2") (pintype "passive"))
      (node (ref "D1") (pin "A") (pinfunction "A_A") (pintype "passive"))
      (node (ref "D17") (pin "A") (pinfunction "A_A") (pintype "passive"))
      (node (ref "D2") (pin "A") (pinfunction "A_A") (pintype "passive"))
      (node (ref "D3") (pin "A") (pinfunction "A_A") (pintype "passive"))
      (node (ref "D4") (pin "A") (pinfunction "A_A") (pintype "passive"))
      (node (ref "D5") (pin "A") (pinfunction "A_A") (pintype "passive"))
      (node (ref "D6") (pin "A") (pinfunction "A_A") (pintype "passive"))
      (node (ref "D7") (pin "A") (pinfunction "A_A") (pintype "passive"))
      (node (ref "IC1") (pin "3") (pinfunction "GND_3") (pintype "power_in"))
      (node (ref "IC1") (pin "7") (pinfunction "A0_7") (pintype "passive"))
      (node (ref "IC10") (pin "8") (pinfunction "GND_8") (pintype "power_in"))
      (node (ref "IC11") (pin "8") (pinfunction "GND_8") (pintype "power_in"))
      (node (ref "IC2") (pin "3") (pinfunction "GND_3") (pintype "power_in"))
      (node (ref "IC3") (pin "3") (pinfunction "GND_3") (pintype "power_in"))
      (node (ref "IC4") (pin "3") (pinfunction "GND_3") (pintype "power_in"))
      (node (ref "IC5") (pin "3") (pinfunction "GND_3") (pintype "power_in"))
      (node (ref "IC5") (pin "7") (pinfunction "A0_7") (pintype "passive"))
      (node (ref "IC6") (pin "3") (pinfunction "GND_3") (pintype "power_in"))
      (node (ref "IC7") (pin "3") (pinfunction "GND_3") (pintype "power_in"))
      (node (ref "IC8") (pin "3") (pinfunction "GND_3") (pintype "power_in"))
      (node (ref "IC9") (pin "10") (pinfunction "VSS_10") (pintype "power_in"))
      (node (ref "IC9") (pin "17") (pinfunction "A2_17") (pintype "passive"))
      (node (ref "J1") (pin "1") (pinfunction "1_1") (pintype "power_in"))
      (node (ref "K1") (pin "14") (pinfunction "14_14") (pintype "passive"))
      (node (ref "K1") (pin "20") (pinfunction "20_20") (pintype "passive"))
      (node (ref "K1") (pin "25") (pinfunction "25_25") (pintype "passive"))
      (node (ref "K1") (pin "30") (pinfunction "30_30") (pintype "passive"))
      (node (ref "K1") (pin "34") (pinfunction "34_34") (pintype "passive"))
      (node (ref "K1") (pin "39") (pinfunction "39_39") (pintype "passive"))
      (node (ref "K1") (pin "6") (pinfunction "6_6") (pintype "passive"))
      (node (ref "K1") (pin "9") (pinfunction "9_9") (pintype "passive"))
      (node (ref "LSP10") (pin "MP") (pinfunction "MP_MP") (pintype "passive"))
      (node (ref "LSP11") (pin "MP") (pinfunction "MP_MP") (pintype "passive"))
      (node (ref "LSP12") (pin "MP") (pinfunction "MP_MP") (pintype "passive"))
      (node (ref "LSP13") (pin "MP") (pinfunction "MP_MP") (pintype "passive"))
      (node (ref "LSP14") (pin "MP") (pinfunction "MP_MP") (pintype "passive"))
      (node (ref "LSP15") (pin "MP") (pinfunction "MP_MP") (pintype "passive"))
      (node (ref "LSP16") (pin "MP") (pinfunction "MP_MP") (pintype "passive"))
      (node (ref "LSP18") (pin "MP") (pinfunction "MP_MP") (pintype "passive"))
      (node (ref "LSP9") (pin "MP") (pinfunction "MP_MP") (pintype "passive"))
      (node (ref "R12") (pin "1") (pinfunction "1_1") (pintype "passive"))
      (node (ref "R13") (pin "1") (pinfunction "1_1") (pintype "passive"))
      (node (ref "R14") (pin "1") (pinfunction "1_1") (pintype "passive"))
      (node (ref "R15") (pin "1") (pinfunction "1_1") (pintype "passive"))
      (node (ref "R16") (pin "1") (pinfunction "1_1") (pintype "passive"))
      (node (ref "R17") (pin "1") (pinfunction "1_1") (pintype "passive"))
      (node (ref "R18") (pin "1") (pinfunction "1_1") (pintype "passive"))
      (node (ref "R19") (pin "1") (pinfunction "1_1") (pintype "passive"))
      (node (ref "SJ1") (pin "3") (pinfunction "3_3") (pintype "passive"))
      (node (ref "SJ2") (pin "3") (pinfunction "3_3") (pintype "passive"))
      (node (ref "U1") (pin "1") (pinfunction "A0_1") (pintype "input"))
      (node (ref "U1") (pin "2") (pinfunction "A1_2") (pintype "input"))
      (node (ref "U1") (pin "3") (pinfunction "A2_3") (pintype "input"))
      (node (ref "U1") (pin "4") (pinfunction "GND_4") (pintype "power_in"))
    )
    (net (code "48") (name "Net-(IC1-A1)") (class "Default")
      (node (ref "IC1") (pin "8") (pinfunction "A1_8") (pintype "passive"))
      (node (ref "R43") (pin "2") (pinfunction "2_2") (pintype "passive"))
    )
    (net (code "49") (name "Net-(IC1-VIN+)") (class "Default")
      (node (ref "IC1") (pin "1") (pinfunction "VIN+_1") (pintype "input"))
      (node (ref "Q1") (pin "3") (pinfunction "D_3") (pintype "passive"))
      (node (ref "R4") (pin "1") (pinfunction "1_1") (pintype "passive"))
    )
    (net (code "50") (name "Net-(IC1-VIN-)") (class "Default")
      (node (ref "D17") (pin "C") (pinfunction "C_C") (pintype "passive"))
      (node (ref "IC1") (pin "2") (pinfunction "VIN-_2") (pintype "input"))
      (node (ref "LSP1") (pin "MP") (pinfunction "MP_MP") (pintype "passive"))
      (node (ref "R12") (pin "2") (pinfunction "2_2") (pintype "passive"))
      (node (ref "R4") (pin "2") (pinfunction "2_2") (pintype "passive"))
    )
    (net (code "51") (name "Net-(IC2-A0)") (class "Default")
      (node (ref "IC2") (pin "7") (pinfunction "A0_7") (pintype "passive"))
      (node (ref "R41") (pin "2") (pinfunction "2_2") (pintype "passive"))
    )
    (net (code "52") (name "Net-(IC2-A1)") (class "Default")
      (node (ref "IC2") (pin "8") (pinfunction "A1_8") (pintype "passive"))
      (node (ref "R44") (pin "2") (pinfunction "2_2") (pintype "passive"))
    )
    (net (code "53") (name "Net-(IC2-VIN+)") (class "Default")
      (node (ref "IC2") (pin "1") (pinfunction "VIN+_1") (pintype "input"))
      (node (ref "Q2") (pin "3") (pinfunction "D_3") (pintype "passive"))
      (node (ref "R5") (pin "1") (pinfunction "1_1") (pintype "passive"))
    )
    (net (code "54") (name "Net-(IC2-VIN-)") (class "Default")
      (node (ref "D1") (pin "C") (pinfunction "C_C") (pintype "passive"))
      (node (ref "IC2") (pin "2") (pinfunction "VIN-_2") (pintype "input"))
      (node (ref "LSP2") (pin "MP") (pinfunction "MP_MP") (pintype "passive"))
      (node (ref "R13") (pin "2") (pinfunction "2_2") (pintype "passive"))
      (node (ref "R5") (pin "2") (pinfunction "2_2") (pintype "passive"))
    )
    (net (code "55") (name "Net-(IC3-A0)") (class "Default")
      (node (ref "IC3") (pin "7") (pinfunction "A0_7") (pintype "passive"))
      (node (ref "IC3") (pin "8") (pinfunction "A1_8") (pintype "passive"))
      (node (ref "R45") (pin "2") (pinfunction "2_2") (pintype "passive"))
    )
    (net (code "56") (name "Net-(IC3-VIN+)") (class "Default")
      (node (ref "IC3") (pin "1") (pinfunction "VIN+_1") (pintype "input"))
      (node (ref "Q3") (pin "3") (pinfunction "D_3") (pintype "passive"))
      (node (ref "R6") (pin "1") (pinfunction "1_1") (pintype "passive"))
    )
    (net (code "57") (name "Net-(IC3-VIN-)") (class "Default")
      (node (ref "D2") (pin "C") (pinfunction "C_C") (pintype "passive"))
      (node (ref "IC3") (pin "2") (pinfunction "VIN-_2") (pintype "input"))
      (node (ref "LSP3") (pin "MP") (pinfunction "MP_MP") (pintype "passive"))
      (node (ref "R14") (pin "2") (pinfunction "2_2") (pintype "passive"))
      (node (ref "R6") (pin "2") (pinfunction "2_2") (pintype "passive"))
    )
    (net (code "58") (name "Net-(IC4-A0)") (class "Default")
      (node (ref "IC4") (pin "7") (pinfunction "A0_7") (pintype "passive"))
      (node (ref "R46") (pin "2") (pinfunction "2_2") (pintype "passive"))
    )
    (net (code "59") (name "Net-(IC4-A1)") (class "Default")
      (node (ref "IC4") (pin "8") (pinfunction "A1_8") (pintype "passive"))
      (node (ref "R47") (pin "2") (pinfunction "2_2") (pintype "passive"))
    )
    (net (code "60") (name "Net-(IC4-VIN+)") (class "Default")
      (node (ref "IC4") (pin "1") (pinfunction "VIN+_1") (pintype "input"))
      (node (ref "Q4") (pin "3") (pinfunction "D_3") (pintype "passive"))
      (node (ref "R7") (pin "1") (pinfunction "1_1") (pintype "passive"))
    )
    (net (code "61") (name "Net-(IC4-VIN-)") (class "Default")
      (node (ref "D3") (pin "C") (pinfunction "C_C") (pintype "passive"))
      (node (ref "IC4") (pin "2") (pinfunction "VIN-_2") (pintype "input"))
      (node (ref "LSP4") (pin "MP") (pinfunction "MP_MP") (pintype "passive"))
      (node (ref "R15") (pin "2") (pinfunction "2_2") (pintype "passive"))
      (node (ref "R7") (pin "2") (pinfunction "2_2") (pintype "passive"))
    )
    (net (code "62") (name "Net-(IC5-A1)") (class "Default")
      (node (ref "IC5") (pin "8") (pinfunction "A1_8") (pintype "passive"))
      (node (ref "R48") (pin "2") (pinfunction "2_2") (pintype "passive"))
    )
    (net (code "63") (name "Net-(IC5-VIN+)") (class "Default")
      (node (ref "IC5") (pin "1") (pinfunction "VIN+_1") (pintype "input"))
      (node (ref "Q5") (pin "3") (pinfunction "D_3") (pintype "passive"))
      (node (ref "R8") (pin "1") (pinfunction "1_1") (pintype "passive"))
    )
    (net (code "64") (name "Net-(IC5-VIN-)") (class "Default")
      (node (ref "D4") (pin "C") (pinfunction "C_C") (pintype "passive"))
      (node (ref "IC5") (pin "2") (pinfunction "VIN-_2") (pintype "input"))
      (node (ref "LSP7") (pin "MP") (pinfunction "MP_MP") (pintype "passive"))
      (node (ref "R16") (pin "2") (pinfunction "2_2") (pintype "passive"))
      (node (ref "R8") (pin "2") (pinfunction "2_2") (pintype "passive"))
    )
    (net (code "65") (name "Net-(IC6-A0)") (class "Default")
      (node (ref "IC6") (pin "7") (pinfunction "A0_7") (pintype "passive"))
      (node (ref "R42") (pin "2") (pinfunction "2_2") (pintype "passive"))
    )
    (net (code "66") (name "Net-(IC6-A1)") (class "Default")
      (node (ref "IC6") (pin "8") (pinfunction "A1_8") (pintype "passive"))
      (node (ref "R49") (pin "2") (pinfunction "2_2") (pintype "passive"))
    )
    (net (code "67") (name "Net-(IC6-VIN+)") (class "Default")
      (node (ref "IC6") (pin "1") (pinfunction "VIN+_1") (pintype "input"))
      (node (ref "Q6") (pin "3") (pinfunction "D_3") (pintype "passive"))
      (node (ref "R9") (pin "1") (pinfunction "1_1") (pintype "passive"))
    )
    (net (code "68") (name "Net-(IC6-VIN-)") (class "Default")
      (node (ref "D5") (pin "C") (pinfunction "C_C") (pintype "passive"))
      (node (ref "IC6") (pin "2") (pinfunction "VIN-_2") (pintype "input"))
      (node (ref "LSP8") (pin "MP") (pinfunction "MP_MP") (pintype "passive"))
      (node (ref "R17") (pin "2") (pinfunction "2_2") (pintype "passive"))
      (node (ref "R9") (pin "2") (pinfunction "2_2") (pintype "passive"))
    )
    (net (code "69") (name "Net-(IC7-A0)") (class "Default")
      (node (ref "IC7") (pin "7") (pinfunction "A0_7") (pintype "passive"))
      (node (ref "R50") (pin "1") (pinfunction "1_1") (pintype "passive"))
    )
    (net (code "70") (name "Net-(IC7-A1)") (class "Default")
      (node (ref "IC7") (pin "8") (pinfunction "A1_8") (pintype "passive"))
      (node (ref "R51") (pin "1") (pinfunction "1_1") (pintype "passive"))
    )
    (net (code "71") (name "Net-(IC7-VIN+)") (class "Default")
      (node (ref "IC7") (pin "1") (pinfunction "VIN+_1") (pintype "input"))
      (node (ref "Q7") (pin "3") (pinfunction "D_3") (pintype "passive"))
      (node (ref "R10") (pin "1") (pinfunction "1_1") (pintype "passive"))
    )
    (net (code "72") (name "Net-(IC7-VIN-)") (class "Default")
      (node (ref "D6") (pin "C") (pinfunction "C_C") (pintype "passive"))
      (node (ref "IC7") (pin "2") (pinfunction "VIN-_2") (pintype "input"))
      (node (ref "LSP6") (pin "MP") (pinfunction "MP_MP") (pintype "passive"))
      (node (ref "R10") (pin "2") (pinfunction "2_2") (pintype "passive"))
      (node (ref "R18") (pin "2") (pinfunction "2_2") (pintype "passive"))
    )
    (net (code "73") (name "Net-(IC8-A0)") (class "Default")
      (node (ref "IC8") (pin "7") (pinfunction "A0_7") (pintype "passive"))
      (node (ref "IC8") (pin "8") (pinfunction "A1_8") (pintype "passive"))
      (node (ref "R40") (pin "2") (pinfunction "2_2") (pintype "passive"))
    )
    (net (code "74") (name "Net-(IC8-VIN+)") (class "Default")
      (node (ref "IC8") (pin "1") (pinfunction "VIN+_1") (pintype "input"))
      (node (ref "Q8") (pin "3") (pinfunction "D_3") (pintype "passive"))
      (node (ref "R11") (pin "1") (pinfunction "1_1") (pintype "passive"))
    )
    (net (code "75") (name "Net-(IC8-VIN-)") (class "Default")
      (node (ref "D7") (pin "C") (pinfunction "C_C") (pintype "passive"))
      (node (ref "IC8") (pin "2") (pinfunction "VIN-_2") (pintype "input"))
      (node (ref "LSP5") (pin "MP") (pinfunction "MP_MP") (pintype "passive"))
      (node (ref "R11") (pin "2") (pinfunction "2_2") (pintype "passive"))
      (node (ref "R19") (pin "2") (pinfunction "2_2") (pintype "passive"))
    )
    (net (code "76") (name "Net-(IC9-A0)") (class "Default")
      (node (ref "IC9") (pin "15") (pinfunction "A0_15") (pintype "passive"))
      (node (ref "SJ2") (pin "2") (pinfunction "2_2") (pintype "passive"))
    )
    (net (code "77") (name "Net-(IC9-A1)") (class "Default")
      (node (ref "IC9") (pin "16") (pinfunction "A1_16") (pintype "passive"))
      (node (ref "SJ1") (pin "2") (pinfunction "2_2") (pintype "passive"))
    )
    (net (code "78") (name "Net-(R38-Pad1)") (class "Default")
      (node (ref "R38") (pin "1") (pinfunction "1_1") (pintype "passive"))
      (node (ref "SJ1") (pin "1") (pinfunction "1_1") (pintype "passive"))
    )
    (net (code "79") (name "Net-(R39-Pad1)") (class "Default")
      (node (ref "R39") (pin "1") (pinfunction "1_1") (pintype "passive"))
      (node (ref "SJ2") (pin "1") (pinfunction "1_1") (pintype "passive"))
    )
    (net (code "80") (name "Net-(U1-SCL)") (class "Default")
      (node (ref "K1") (pin "28") (pinfunction "28_28") (pintype "passive"))
      (node (ref "R1") (pin "1") (pinfunction "1_1") (pintype "passive"))
      (node (ref "U1") (pin "6") (pinfunction "SCL_6") (pintype "input"))
    )
    (net (code "81") (name "Net-(U1-SDA)") (class "Default")
      (node (ref "K1") (pin "27") (pinfunction "27_27") (pintype "passive"))
      (node (ref "R2") (pin "1") (pinfunction "1_1") (pintype "passive"))
      (node (ref "U1") (pin "5") (pinfunction "SDA_5") (pintype "bidirectional"))
    )
    (net (code "82") (name "Net-(U1-WP)") (class "Default")
      (node (ref "CFG") (pin "1") (pinfunction "1_1") (pintype "passive"))
      (node (ref "R3") (pin "1") (pinfunction "1_1") (pintype "passive"))
      (node (ref "U1") (pin "7") (pinfunction "WP_7") (pintype "input"))
    )
    (net (code "83") (name "unconnected-(IC9-GPA7-Pad28)") (class "Default")
      (node (ref "IC9") (pin "28") (pinfunction "GPA7_28") (pintype "passive"))
    )
    (net (code "84") (name "unconnected-(IC9-GPB7-Pad8)") (class "Default")
      (node (ref "IC9") (pin "8") (pinfunction "GPB7_8") (pintype "passive"))
    )
    (net (code "85") (name "unconnected-(IC9-INTA-Pad20)") (class "Default")
      (node (ref "IC9") (pin "20") (pinfunction "INTA_20") (pintype "input"))
    )
    (net (code "86") (name "unconnected-(IC9-INTB-Pad19)") (class "Default")
      (node (ref "IC9") (pin "19") (pinfunction "INTB_19") (pintype "input"))
    )
    (net (code "87") (name "unconnected-(IC9-NC-Pad11)") (class "Default")
      (node (ref "IC9") (pin "11") (pinfunction "NC_11") (pintype "no_connect"))
    )
    (net (code "88") (name "unconnected-(IC9-NC_1-Pad14)") (class "Default")
      (node (ref "IC9") (pin "14") (pinfunction "NC_1_14") (pintype "passive"))
    )
    (net (code "89") (name "unconnected-(K1-Pad7)") (class "Default")
      (node (ref "K1") (pin "7") (pinfunction "7_7") (pintype "passive"))
    )
    (net (code "90") (name "unconnected-(K1-Pad8)") (class "Default")
      (node (ref "K1") (pin "8") (pinfunction "8_8") (pintype "passive"))
    )
    (net (code "91") (name "unconnected-(K1-Pad10)") (class "Default")
      (node (ref "K1") (pin "10") (pinfunction "10_10") (pintype "passive"))
    )
    (net (code "92") (name "unconnected-(K1-Pad11)") (class "Default")
      (node (ref "K1") (pin "11") (pinfunction "11_11") (pintype "passive"))
    )
    (net (code "93") (name "unconnected-(K1-Pad12)") (class "Default")
      (node (ref "K1") (pin "12") (pinfunction "12_12") (pintype "passive"))
    )
    (net (code "94") (name "unconnected-(K1-Pad13)") (class "Default")
      (node (ref "K1") (pin "13") (pinfunction "13_13") (pintype "passive"))
    )
    (net (code "95") (name "unconnected-(K1-Pad15)") (class "Default")
      (node (ref "K1") (pin "15") (pinfunction "15_15") (pintype "passive"))
    )
    (net (code "96") (name "unconnected-(K1-Pad16)") (class "Default")
      (node (ref "K1") (pin "16") (pinfunction "16_16") (pintype "passive"))
    )
    (net (code "97") (name "unconnected-(K1-Pad18)") (class "Default")
      (node (ref "K1") (pin "18") (pinfunction "18_18") (pintype "passive"))
    )
    (net (code "98") (name "unconnected-(K1-Pad19)") (class "Default")
      (node (ref "K1") (pin "19") (pinfunction "19_19") (pintype "passive"))
    )
    (net (code "99") (name "unconnected-(K1-Pad21)") (class "Default")
      (node (ref "K1") (pin "21") (pinfunction "21_21") (pintype "passive"))
    )
    (net (code "100") (name "unconnected-(K1-Pad22)") (class "Default")
      (node (ref "K1") (pin "22") (pinfunction "22_22") (pintype "passive"))
    )
    (net (code "101") (name "unconnected-(K1-Pad23)") (class "Default")
      (node (ref "K1") (pin "23") (pinfunction "23_23") (pintype "passive"))
    )
    (net (code "102") (name "unconnected-(K1-Pad24)") (class "Default")
      (node (ref "K1") (pin "24") (pinfunction "24_24") (pintype "passive"))
    )
    (net (code "103") (name "unconnected-(K1-Pad26)") (class "Default")
      (node (ref "K1") (pin "26") (pinfunction "26_26") (pintype "passive"))
    )
    (net (code "104") (name "unconnected-(K1-Pad32)") (class "Default")
      (node (ref "K1") (pin "32") (pinfunction "32_32") (pintype "passive"))
    )
    (net (code "105") (name "unconnected-(K1-Pad35)") (class "Default")
      (node (ref "K1") (pin "35") (pinfunction "35_35") (pintype "passive"))
    )
    (net (code "106") (name "unconnected-(K1-Pad36)") (class "Default")
      (node (ref "K1") (pin "36") (pinfunction "36_36") (pintype "passive"))
    )
    (net (code "107") (name "unconnected-(K1-Pad40)") (class "Default")
      (node (ref "K1") (pin "40") (pinfunction "40_40") (pintype "passive"))
    )
  )
)
